# lm709_PCB.net
KiCad netlist of a schematic drawn in EAGLE
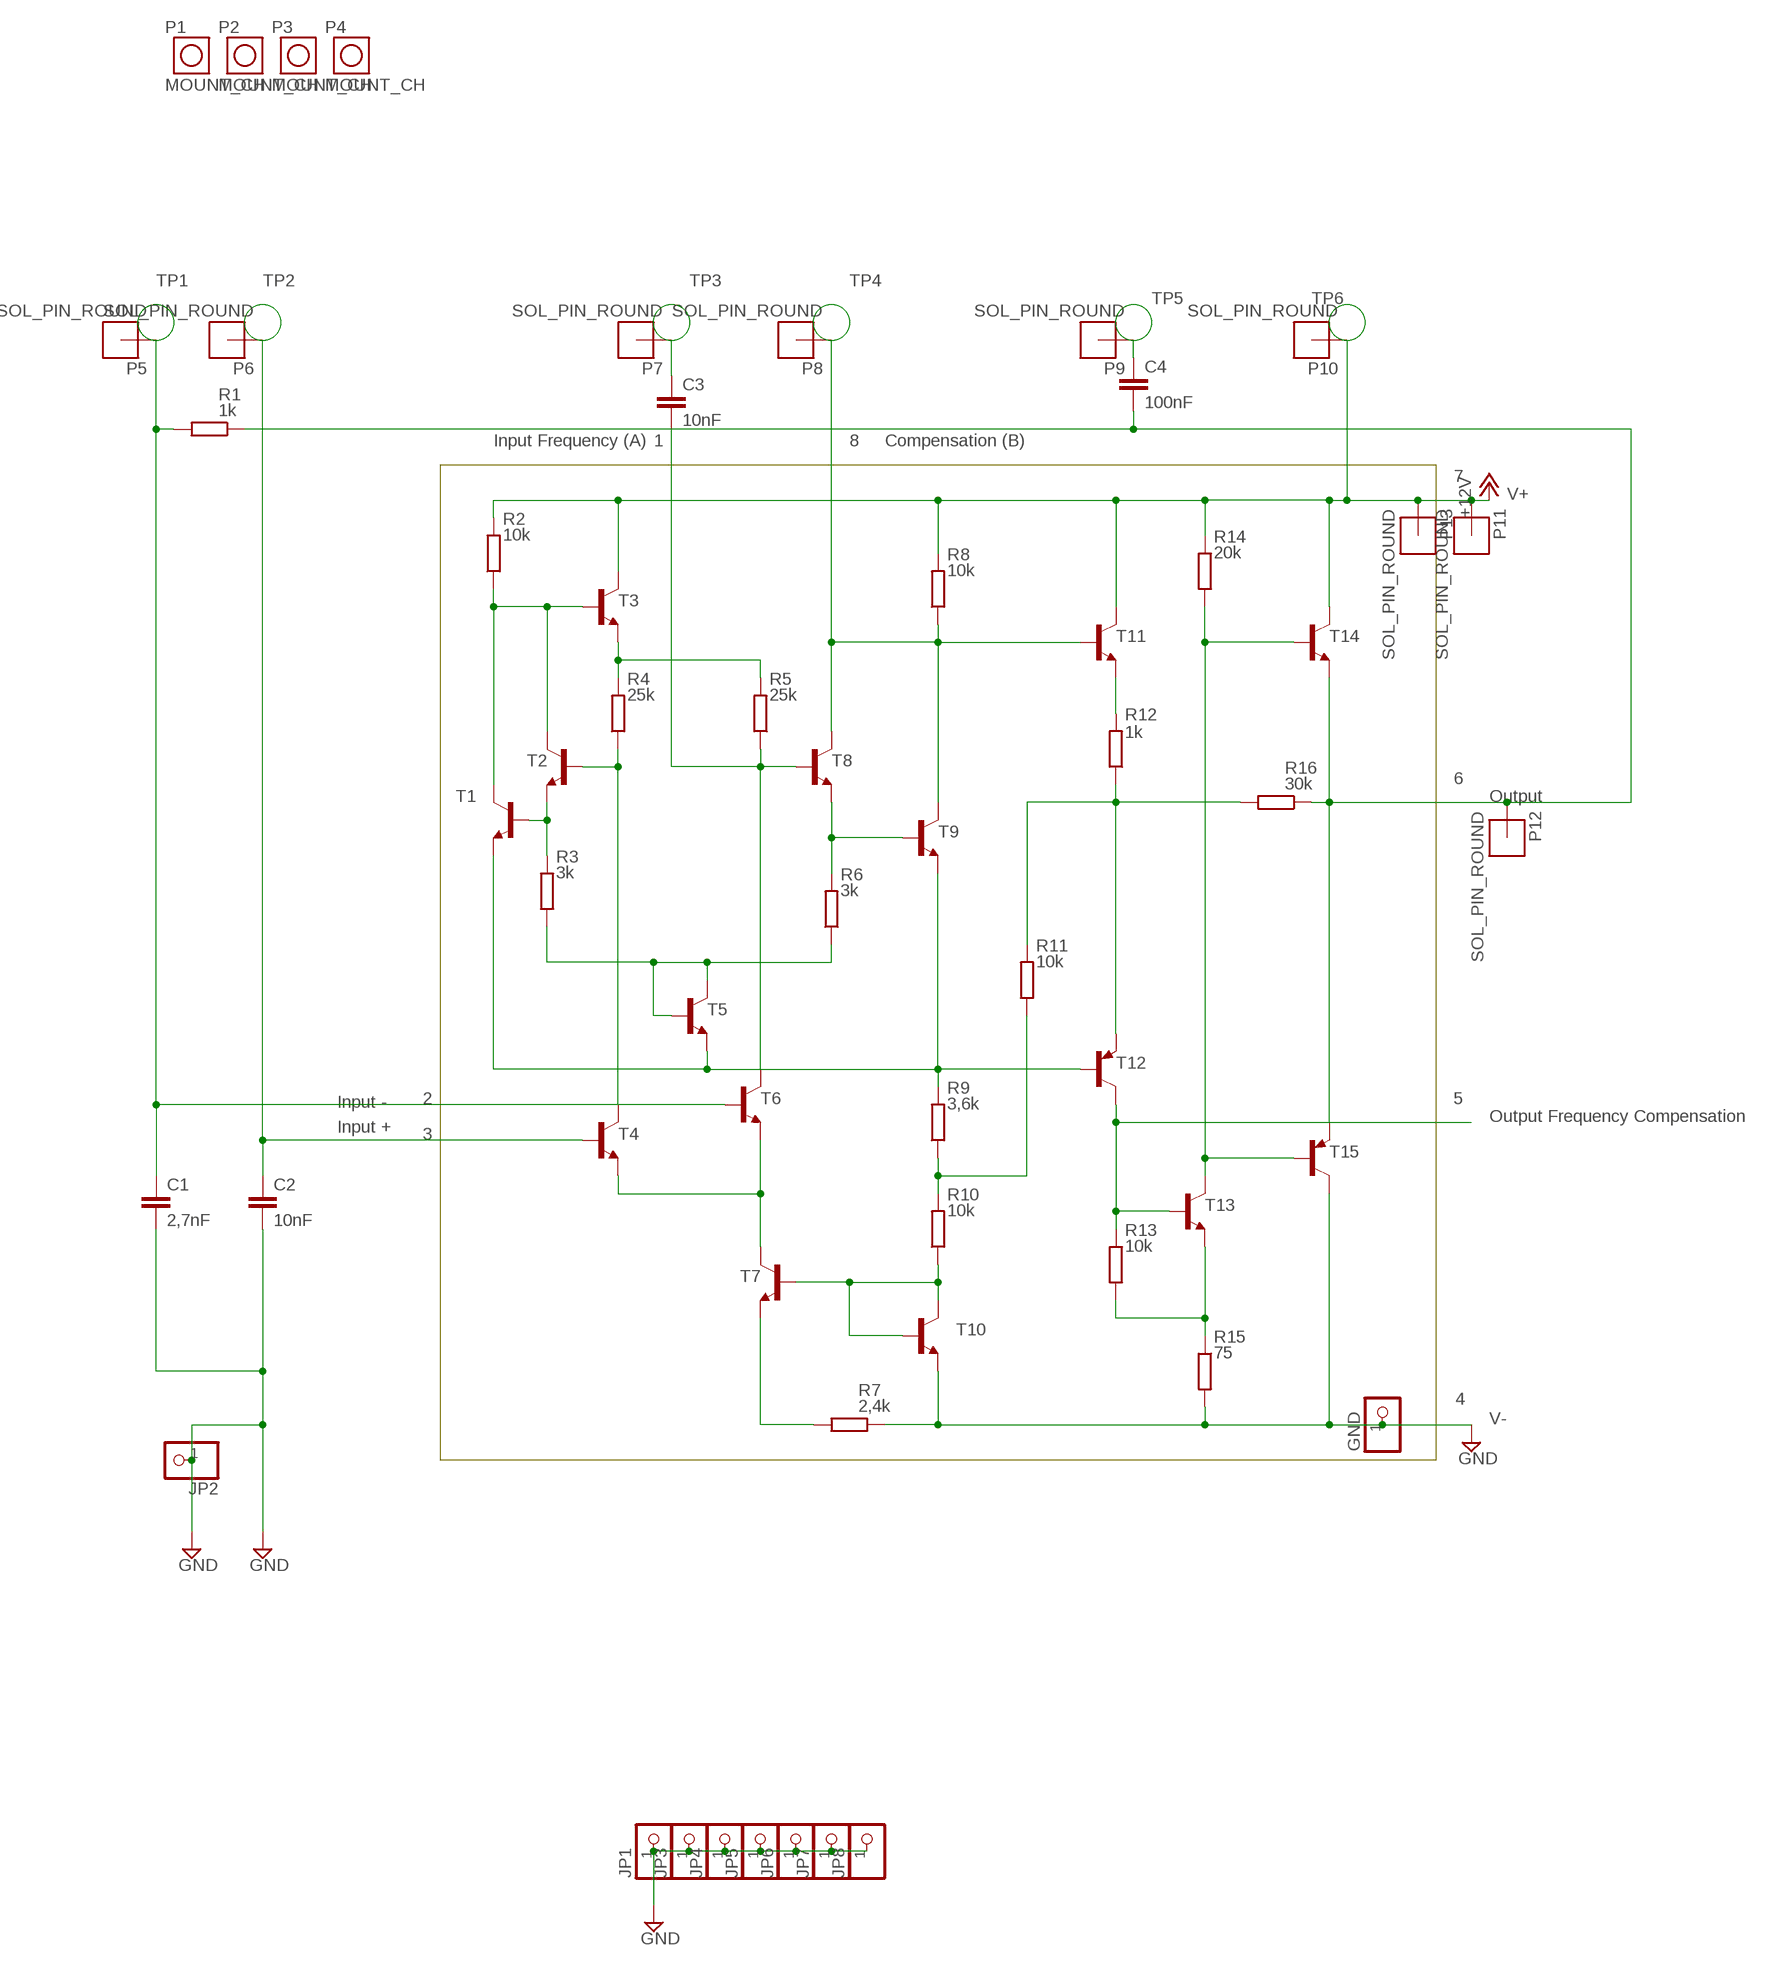
[diagram p0: schematic, sheet 1]

(export (version "E")
  (design (tool "Eeschema 10.0.6"))
  (components
    (comp (ref "C1")
      (value "2,7nF")
      (footprint "eagle-import:C050-024X044")
      (libsource (lib "eagle-import") (part "C-EU050-024X044"))
    )
    (comp (ref "C2")
      (value "10nF")
      (footprint "eagle-import:C050-024X044")
      (libsource (lib "eagle-import") (part "C-EU050-024X044"))
    )
    (comp (ref "C3")
      (value "10nF")
      (footprint "eagle-import:C050-024X044")
      (libsource (lib "eagle-import") (part "C-EU050-024X044"))
    )
    (comp (ref "C4")
      (value "100nF")
      (footprint "eagle-import:C050-024X044")
      (libsource (lib "eagle-import") (part "C-EU050-024X044"))
    )
    (comp (ref "GND")
      (value "PINHD-1X1")
      (footprint "eagle-import:1X01")
      (libsource (lib "eagle-import") (part "pinhead_325_PINHD-1X1"))
    )
    (comp (ref "JP1")
      (value "PINHD-1X1")
      (footprint "eagle-import:1X01")
      (libsource (lib "eagle-import") (part "PINHD-1X1"))
    )
    (comp (ref "JP2")
      (value "PINHD-1X1")
      (footprint "eagle-import:1X01")
      (libsource (lib "eagle-import") (part "pinhead_325_PINHD-1X1"))
    )
    (comp (ref "JP3")
      (value "PINHD-1X1")
      (footprint "eagle-import:1X01")
      (libsource (lib "eagle-import") (part "PINHD-1X1"))
    )
    (comp (ref "JP4")
      (value "PINHD-1X1")
      (footprint "eagle-import:1X01")
      (libsource (lib "eagle-import") (part "PINHD-1X1"))
    )
    (comp (ref "JP5")
      (value "PINHD-1X1")
      (footprint "eagle-import:1X01")
      (libsource (lib "eagle-import") (part "PINHD-1X1"))
    )
    (comp (ref "JP6")
      (value "PINHD-1X1")
      (footprint "eagle-import:1X01")
      (libsource (lib "eagle-import") (part "PINHD-1X1"))
    )
    (comp (ref "JP7")
      (value "PINHD-1X1")
      (footprint "eagle-import:1X01")
      (libsource (lib "eagle-import") (part "PINHD-1X1"))
    )
    (comp (ref "JP8")
      (value "PINHD-1X1")
      (footprint "eagle-import:1X01")
      (libsource (lib "eagle-import") (part "PINHD-1X1"))
    )
    (comp (ref "P1")
      (value "MOUNT_CH")
      (footprint "eagle-import:MOUNT_CH32")
      (libsource (lib "eagle-import") (part "MOUNT_CH"))
    )
    (comp (ref "P2")
      (value "MOUNT_CH")
      (footprint "eagle-import:MOUNT_CH32")
      (libsource (lib "eagle-import") (part "MOUNT_CH"))
    )
    (comp (ref "P3")
      (value "MOUNT_CH")
      (footprint "eagle-import:MOUNT_CH32")
      (libsource (lib "eagle-import") (part "MOUNT_CH"))
    )
    (comp (ref "P4")
      (value "MOUNT_CH")
      (footprint "eagle-import:MOUNT_CH32")
      (libsource (lib "eagle-import") (part "MOUNT_CH"))
    )
    (comp (ref "P5")
      (value "SOL_PIN_ROUND")
      (footprint "eagle-import:SOL_PAD_ROUND")
      (libsource (lib "eagle-import") (part "SOL_PIN_ROUND"))
    )
    (comp (ref "P6")
      (value "SOL_PIN_ROUND")
      (footprint "eagle-import:SOL_PAD_ROUND")
      (libsource (lib "eagle-import") (part "SOL_PIN_ROUND"))
    )
    (comp (ref "P7")
      (value "SOL_PIN_ROUND")
      (footprint "eagle-import:SOL_PAD_ROUND")
      (libsource (lib "eagle-import") (part "SOL_PIN_ROUND"))
    )
    (comp (ref "P8")
      (value "SOL_PIN_ROUND")
      (footprint "eagle-import:SOL_PAD_ROUND")
      (libsource (lib "eagle-import") (part "SOL_PIN_ROUND"))
    )
    (comp (ref "P9")
      (value "SOL_PIN_ROUND")
      (footprint "eagle-import:SOL_PAD_ROUND")
      (libsource (lib "eagle-import") (part "SOL_PIN_ROUND"))
    )
    (comp (ref "P10")
      (value "SOL_PIN_ROUND")
      (footprint "eagle-import:SOL_PAD_ROUND")
      (libsource (lib "eagle-import") (part "SOL_PIN_ROUND"))
    )
    (comp (ref "P11")
      (value "SOL_PIN_ROUND")
      (footprint "eagle-import:SOL_PAD_ROUND")
      (libsource (lib "eagle-import") (part "SOL_PIN_ROUND"))
    )
    (comp (ref "P12")
      (value "SOL_PIN_ROUND")
      (footprint "eagle-import:SOL_PAD_ROUND")
      (libsource (lib "eagle-import") (part "SOL_PIN_ROUND"))
    )
    (comp (ref "P13")
      (value "SOL_PIN_ROUND")
      (footprint "eagle-import:SOL_PAD_ROUND")
      (libsource (lib "eagle-import") (part "SOL_PIN_ROUND"))
    )
    (comp (ref "R1")
      (value "1k")
      (footprint "eagle-import:0207_10")
      (libsource (lib "eagle-import") (part "R-EU_0207/10"))
    )
    (comp (ref "R2")
      (value "10k")
      (footprint "eagle-import:0207_10")
      (libsource (lib "eagle-import") (part "R-EU_0207/10"))
    )
    (comp (ref "R3")
      (value "3k")
      (footprint "eagle-import:0207_10")
      (libsource (lib "eagle-import") (part "R-EU_0207/10"))
    )
    (comp (ref "R4")
      (value "25k")
      (footprint "eagle-import:0207_10")
      (libsource (lib "eagle-import") (part "R-EU_0207/10"))
    )
    (comp (ref "R5")
      (value "25k")
      (footprint "eagle-import:0207_10")
      (libsource (lib "eagle-import") (part "R-EU_0207/10"))
    )
    (comp (ref "R6")
      (value "3k")
      (footprint "eagle-import:0207_10")
      (libsource (lib "eagle-import") (part "R-EU_0207/10"))
    )
    (comp (ref "R7")
      (value "2,4k")
      (footprint "eagle-import:0207_10")
      (libsource (lib "eagle-import") (part "R-EU_0207/10"))
    )
    (comp (ref "R8")
      (value "10k")
      (footprint "eagle-import:0207_10")
      (libsource (lib "eagle-import") (part "R-EU_0207/10"))
    )
    (comp (ref "R9")
      (value "3,6k")
      (footprint "eagle-import:0207_10")
      (libsource (lib "eagle-import") (part "R-EU_0207/10"))
    )
    (comp (ref "R10")
      (value "10k")
      (footprint "eagle-import:0207_10")
      (libsource (lib "eagle-import") (part "R-EU_0207/10"))
    )
    (comp (ref "R11")
      (value "10k")
      (footprint "eagle-import:0207_10")
      (libsource (lib "eagle-import") (part "R-EU_0207/10"))
    )
    (comp (ref "R12")
      (value "1k")
      (footprint "eagle-import:0207_10")
      (libsource (lib "eagle-import") (part "R-EU_0207/10"))
    )
    (comp (ref "R13")
      (value "10k")
      (footprint "eagle-import:0207_10")
      (libsource (lib "eagle-import") (part "R-EU_0207/10"))
    )
    (comp (ref "R14")
      (value "20k")
      (footprint "eagle-import:0207_10")
      (libsource (lib "eagle-import") (part "R-EU_0207/10"))
    )
    (comp (ref "R15")
      (value "75")
      (footprint "eagle-import:0207_10")
      (libsource (lib "eagle-import") (part "R-EU_0207/10"))
    )
    (comp (ref "R16")
      (value "30k")
      (footprint "eagle-import:0207_10")
      (libsource (lib "eagle-import") (part "R-EU_0207/10"))
    )
    (comp (ref "T1")
      (value "2N3904-NPN-TO92-EBC")
      (footprint "eagle-import:TO92-EBC")
      (libsource (lib "eagle-import") (part "-NPN-TO92-EBC2N3904"))
    )
    (comp (ref "T2")
      (value "2N3904-NPN-TO92-EBC")
      (footprint "eagle-import:TO92-EBC")
      (libsource (lib "eagle-import") (part "-NPN-TO92-EBC2N3904"))
    )
    (comp (ref "T3")
      (value "2N3904-NPN-TO92-EBC")
      (footprint "eagle-import:TO92-EBC")
      (libsource (lib "eagle-import") (part "-NPN-TO92-EBC2N3904"))
    )
    (comp (ref "T4")
      (value "2N3904-NPN-TO92-EBC")
      (footprint "eagle-import:TO92-EBC")
      (libsource (lib "eagle-import") (part "-NPN-TO92-EBC2N3904"))
    )
    (comp (ref "T5")
      (value "2N3904-NPN-TO92-EBC")
      (footprint "eagle-import:TO92-EBC")
      (libsource (lib "eagle-import") (part "-NPN-TO92-EBC2N3904"))
    )
    (comp (ref "T6")
      (value "2N3904-NPN-TO92-EBC")
      (footprint "eagle-import:TO92-EBC")
      (libsource (lib "eagle-import") (part "-NPN-TO92-EBC2N3904"))
    )
    (comp (ref "T7")
      (value "2N3904-NPN-TO92-EBC")
      (footprint "eagle-import:TO92-EBC")
      (libsource (lib "eagle-import") (part "-NPN-TO92-EBC2N3904"))
    )
    (comp (ref "T8")
      (value "2N3904-NPN-TO92-EBC")
      (footprint "eagle-import:TO92-EBC")
      (libsource (lib "eagle-import") (part "-NPN-TO92-EBC2N3904"))
    )
    (comp (ref "T9")
      (value "2N3904-NPN-TO92-EBC")
      (footprint "eagle-import:TO92-EBC")
      (libsource (lib "eagle-import") (part "-NPN-TO92-EBC2N3904"))
    )
    (comp (ref "T10")
      (value "2N3904-NPN-TO92-EBC")
      (footprint "eagle-import:TO92-EBC")
      (libsource (lib "eagle-import") (part "-NPN-TO92-EBC2N3904"))
    )
    (comp (ref "T11")
      (value "2N3904-NPN-TO92-EBC")
      (footprint "eagle-import:TO92-EBC")
      (libsource (lib "eagle-import") (part "-NPN-TO92-EBC2N3904"))
    )
    (comp (ref "T12")
      (value "2N3906-PNP-TO92-EBC")
      (footprint "eagle-import:TO92-EBC")
      (libsource (lib "eagle-import") (part "-PNP-TO92-EBC2N3906"))
    )
    (comp (ref "T13")
      (value "2N3904-NPN-TO92-EBC")
      (footprint "eagle-import:TO92-EBC")
      (libsource (lib "eagle-import") (part "-NPN-TO92-EBC2N3904"))
    )
    (comp (ref "T14")
      (value "2N3904-NPN-TO92-EBC")
      (footprint "eagle-import:TO92-EBC")
      (libsource (lib "eagle-import") (part "-NPN-TO92-EBC2N3904"))
    )
    (comp (ref "T15")
      (value "2N3906-PNP-TO92-EBC")
      (footprint "eagle-import:TO92-EBC")
      (libsource (lib "eagle-import") (part "-PNP-TO92-EBC2N3906"))
    )
  )
  (nets
    (net (code "1") (name "+12V") (class "Default")
      (node (ref "P10") (pin "1") (pinfunction "P$1_1") (pintype "bidirectional"))
      (node (ref "P11") (pin "1") (pinfunction "P$1_1") (pintype "bidirectional"))
      (node (ref "P13") (pin "1") (pinfunction "P$1_1") (pintype "bidirectional"))
      (node (ref "R14") (pin "2") (pinfunction "2_2") (pintype "passive"))
      (node (ref "R2") (pin "2") (pinfunction "2_2") (pintype "passive"))
      (node (ref "R8") (pin "2") (pinfunction "2_2") (pintype "passive"))
      (node (ref "T11") (pin "C") (pinfunction "C_C") (pintype "passive"))
      (node (ref "T14") (pin "C") (pinfunction "C_C") (pintype "passive"))
      (node (ref "T3") (pin "C") (pinfunction "C_C") (pintype "passive"))
    )
    (net (code "2") (name "GND") (class "Default")
      (node (ref "C1") (pin "2") (pinfunction "2_2") (pintype "passive"))
      (node (ref "C2") (pin "2") (pinfunction "2_2") (pintype "passive"))
      (node (ref "GND") (pin "1") (pinfunction "1_1") (pintype "passive"))
      (node (ref "JP1") (pin "1") (pinfunction "1_1") (pintype "passive"))
      (node (ref "JP2") (pin "1") (pinfunction "1_1") (pintype "passive"))
      (node (ref "JP3") (pin "1") (pinfunction "1_1") (pintype "passive"))
      (node (ref "JP4") (pin "1") (pinfunction "1_1") (pintype "passive"))
      (node (ref "JP5") (pin "1") (pinfunction "1_1") (pintype "passive"))
      (node (ref "JP6") (pin "1") (pinfunction "1_1") (pintype "passive"))
      (node (ref "JP7") (pin "1") (pinfunction "1_1") (pintype "passive"))
      (node (ref "JP8") (pin "1") (pinfunction "1_1") (pintype "passive"))
      (node (ref "R15") (pin "2") (pinfunction "2_2") (pintype "passive"))
      (node (ref "R7") (pin "1") (pinfunction "1_1") (pintype "passive"))
      (node (ref "T10") (pin "E") (pinfunction "E_E") (pintype "passive"))
      (node (ref "T15") (pin "C") (pinfunction "C_C") (pintype "passive"))
    )
    (net (code "3") (name "Net-(C3-Pad2)") (class "Default")
      (node (ref "C3") (pin "2") (pinfunction "2_2") (pintype "passive"))
      (node (ref "R5") (pin "1") (pinfunction "1_1") (pintype "passive"))
      (node (ref "T6") (pin "C") (pinfunction "C_C") (pintype "passive"))
      (node (ref "T8") (pin "B") (pinfunction "B_B") (pintype "passive"))
    )
    (net (code "4") (name "Net-(P5-P$1)") (class "Default")
      (node (ref "C1") (pin "1") (pinfunction "1_1") (pintype "passive"))
      (node (ref "P5") (pin "1") (pinfunction "P$1_1") (pintype "bidirectional"))
      (node (ref "R1") (pin "2") (pinfunction "2_2") (pintype "passive"))
      (node (ref "T6") (pin "B") (pinfunction "B_B") (pintype "passive"))
    )
    (net (code "5") (name "Net-(P6-P$1)") (class "Default")
      (node (ref "C2") (pin "1") (pinfunction "1_1") (pintype "passive"))
      (node (ref "P6") (pin "1") (pinfunction "P$1_1") (pintype "bidirectional"))
      (node (ref "T4") (pin "B") (pinfunction "B_B") (pintype "passive"))
    )
    (net (code "6") (name "Net-(P7-P$1)") (class "Default")
      (node (ref "C3") (pin "1") (pinfunction "1_1") (pintype "passive"))
      (node (ref "P7") (pin "1") (pinfunction "P$1_1") (pintype "bidirectional"))
    )
    (net (code "7") (name "Net-(P8-P$1)") (class "Default")
      (node (ref "P8") (pin "1") (pinfunction "P$1_1") (pintype "bidirectional"))
      (node (ref "R8") (pin "1") (pinfunction "1_1") (pintype "passive"))
      (node (ref "T11") (pin "B") (pinfunction "B_B") (pintype "passive"))
      (node (ref "T8") (pin "C") (pinfunction "C_C") (pintype "passive"))
      (node (ref "T9") (pin "C") (pinfunction "C_C") (pintype "passive"))
    )
    (net (code "8") (name "Net-(P9-P$1)") (class "Default")
      (node (ref "C4") (pin "1") (pinfunction "1_1") (pintype "passive"))
      (node (ref "P9") (pin "1") (pinfunction "P$1_1") (pintype "bidirectional"))
    )
    (net (code "9") (name "Net-(P12-P$1)") (class "Default")
      (node (ref "C4") (pin "2") (pinfunction "2_2") (pintype "passive"))
      (node (ref "P12") (pin "1") (pinfunction "P$1_1") (pintype "bidirectional"))
      (node (ref "R1") (pin "1") (pinfunction "1_1") (pintype "passive"))
      (node (ref "R16") (pin "1") (pinfunction "1_1") (pintype "passive"))
      (node (ref "T14") (pin "E") (pinfunction "E_E") (pintype "passive"))
      (node (ref "T15") (pin "E") (pinfunction "E_E") (pintype "passive"))
    )
    (net (code "10") (name "Net-(R2-Pad1)") (class "Default")
      (node (ref "R2") (pin "1") (pinfunction "1_1") (pintype "passive"))
      (node (ref "T1") (pin "C") (pinfunction "C_C") (pintype "passive"))
      (node (ref "T2") (pin "C") (pinfunction "C_C") (pintype "passive"))
      (node (ref "T3") (pin "B") (pinfunction "B_B") (pintype "passive"))
    )
    (net (code "11") (name "Net-(R3-Pad1)") (class "Default")
      (node (ref "R3") (pin "1") (pinfunction "1_1") (pintype "passive"))
      (node (ref "R6") (pin "1") (pinfunction "1_1") (pintype "passive"))
      (node (ref "T5") (pin "B") (pinfunction "B_B") (pintype "passive"))
      (node (ref "T5") (pin "C") (pinfunction "C_C") (pintype "passive"))
    )
    (net (code "12") (name "Net-(R3-Pad2)") (class "Default")
      (node (ref "R3") (pin "2") (pinfunction "2_2") (pintype "passive"))
      (node (ref "T1") (pin "B") (pinfunction "B_B") (pintype "passive"))
      (node (ref "T2") (pin "E") (pinfunction "E_E") (pintype "passive"))
    )
    (net (code "13") (name "Net-(R4-Pad1)") (class "Default")
      (node (ref "R4") (pin "1") (pinfunction "1_1") (pintype "passive"))
      (node (ref "T2") (pin "B") (pinfunction "B_B") (pintype "passive"))
      (node (ref "T4") (pin "C") (pinfunction "C_C") (pintype "passive"))
    )
    (net (code "14") (name "Net-(R4-Pad2)") (class "Default")
      (node (ref "R4") (pin "2") (pinfunction "2_2") (pintype "passive"))
      (node (ref "R5") (pin "2") (pinfunction "2_2") (pintype "passive"))
      (node (ref "T3") (pin "E") (pinfunction "E_E") (pintype "passive"))
    )
    (net (code "15") (name "Net-(R6-Pad2)") (class "Default")
      (node (ref "R6") (pin "2") (pinfunction "2_2") (pintype "passive"))
      (node (ref "T8") (pin "E") (pinfunction "E_E") (pintype "passive"))
      (node (ref "T9") (pin "B") (pinfunction "B_B") (pintype "passive"))
    )
    (net (code "16") (name "Net-(R7-Pad2)") (class "Default")
      (node (ref "R7") (pin "2") (pinfunction "2_2") (pintype "passive"))
      (node (ref "T7") (pin "E") (pinfunction "E_E") (pintype "passive"))
    )
    (net (code "17") (name "Net-(R9-Pad2)") (class "Default")
      (node (ref "R9") (pin "2") (pinfunction "2_2") (pintype "passive"))
      (node (ref "T1") (pin "E") (pinfunction "E_E") (pintype "passive"))
      (node (ref "T12") (pin "B") (pinfunction "B_B") (pintype "passive"))
      (node (ref "T5") (pin "E") (pinfunction "E_E") (pintype "passive"))
      (node (ref "T9") (pin "E") (pinfunction "E_E") (pintype "passive"))
    )
    (net (code "18") (name "Net-(R10-Pad1)") (class "Default")
      (node (ref "R10") (pin "1") (pinfunction "1_1") (pintype "passive"))
      (node (ref "T10") (pin "B") (pinfunction "B_B") (pintype "passive"))
      (node (ref "T10") (pin "C") (pinfunction "C_C") (pintype "passive"))
      (node (ref "T7") (pin "B") (pinfunction "B_B") (pintype "passive"))
    )
    (net (code "19") (name "Net-(R10-Pad2)") (class "Default")
      (node (ref "R10") (pin "2") (pinfunction "2_2") (pintype "passive"))
      (node (ref "R11") (pin "1") (pinfunction "1_1") (pintype "passive"))
      (node (ref "R9") (pin "1") (pinfunction "1_1") (pintype "passive"))
    )
    (net (code "20") (name "Net-(R11-Pad2)") (class "Default")
      (node (ref "R11") (pin "2") (pinfunction "2_2") (pintype "passive"))
      (node (ref "R12") (pin "1") (pinfunction "1_1") (pintype "passive"))
      (node (ref "R16") (pin "2") (pinfunction "2_2") (pintype "passive"))
      (node (ref "T12") (pin "E") (pinfunction "E_E") (pintype "passive"))
    )
    (net (code "21") (name "Net-(R12-Pad2)") (class "Default")
      (node (ref "R12") (pin "2") (pinfunction "2_2") (pintype "passive"))
      (node (ref "T11") (pin "E") (pinfunction "E_E") (pintype "passive"))
    )
    (net (code "22") (name "Net-(R13-Pad1)") (class "Default")
      (node (ref "R13") (pin "1") (pinfunction "1_1") (pintype "passive"))
      (node (ref "T12") (pin "C") (pinfunction "C_C") (pintype "passive"))
      (node (ref "T13") (pin "B") (pinfunction "B_B") (pintype "passive"))
    )
    (net (code "23") (name "Net-(R13-Pad2)") (class "Default")
      (node (ref "R13") (pin "2") (pinfunction "2_2") (pintype "passive"))
      (node (ref "R15") (pin "1") (pinfunction "1_1") (pintype "passive"))
      (node (ref "T13") (pin "E") (pinfunction "E_E") (pintype "passive"))
    )
    (net (code "24") (name "Net-(R14-Pad1)") (class "Default")
      (node (ref "R14") (pin "1") (pinfunction "1_1") (pintype "passive"))
      (node (ref "T13") (pin "C") (pinfunction "C_C") (pintype "passive"))
      (node (ref "T14") (pin "B") (pinfunction "B_B") (pintype "passive"))
      (node (ref "T15") (pin "B") (pinfunction "B_B") (pintype "passive"))
    )
    (net (code "25") (name "Net-(T4-PadE)") (class "Default")
      (node (ref "T4") (pin "E") (pinfunction "E_E") (pintype "passive"))
      (node (ref "T6") (pin "E") (pinfunction "E_E") (pintype "passive"))
      (node (ref "T7") (pin "C") (pinfunction "C_C") (pintype "passive"))
    )
    (net (code "26") (name "unconnected-(P1-PadP$1)") (class "Default")
      (node (ref "P1") (pin "P$1") (pinfunction "P$1_P$1") (pintype "bidirectional"))
    )
    (net (code "27") (name "unconnected-(P2-PadP$1)") (class "Default")
      (node (ref "P2") (pin "P$1") (pinfunction "P$1_P$1") (pintype "bidirectional"))
    )
    (net (code "28") (name "unconnected-(P3-PadP$1)") (class "Default")
      (node (ref "P3") (pin "P$1") (pinfunction "P$1_P$1") (pintype "bidirectional"))
    )
    (net (code "29") (name "unconnected-(P4-PadP$1)") (class "Default")
      (node (ref "P4") (pin "P$1") (pinfunction "P$1_P$1") (pintype "bidirectional"))
    )
  )
)
